# SR1PCB_2025-01-03.net
KiCad netlist of a schematic drawn in Altium Designer
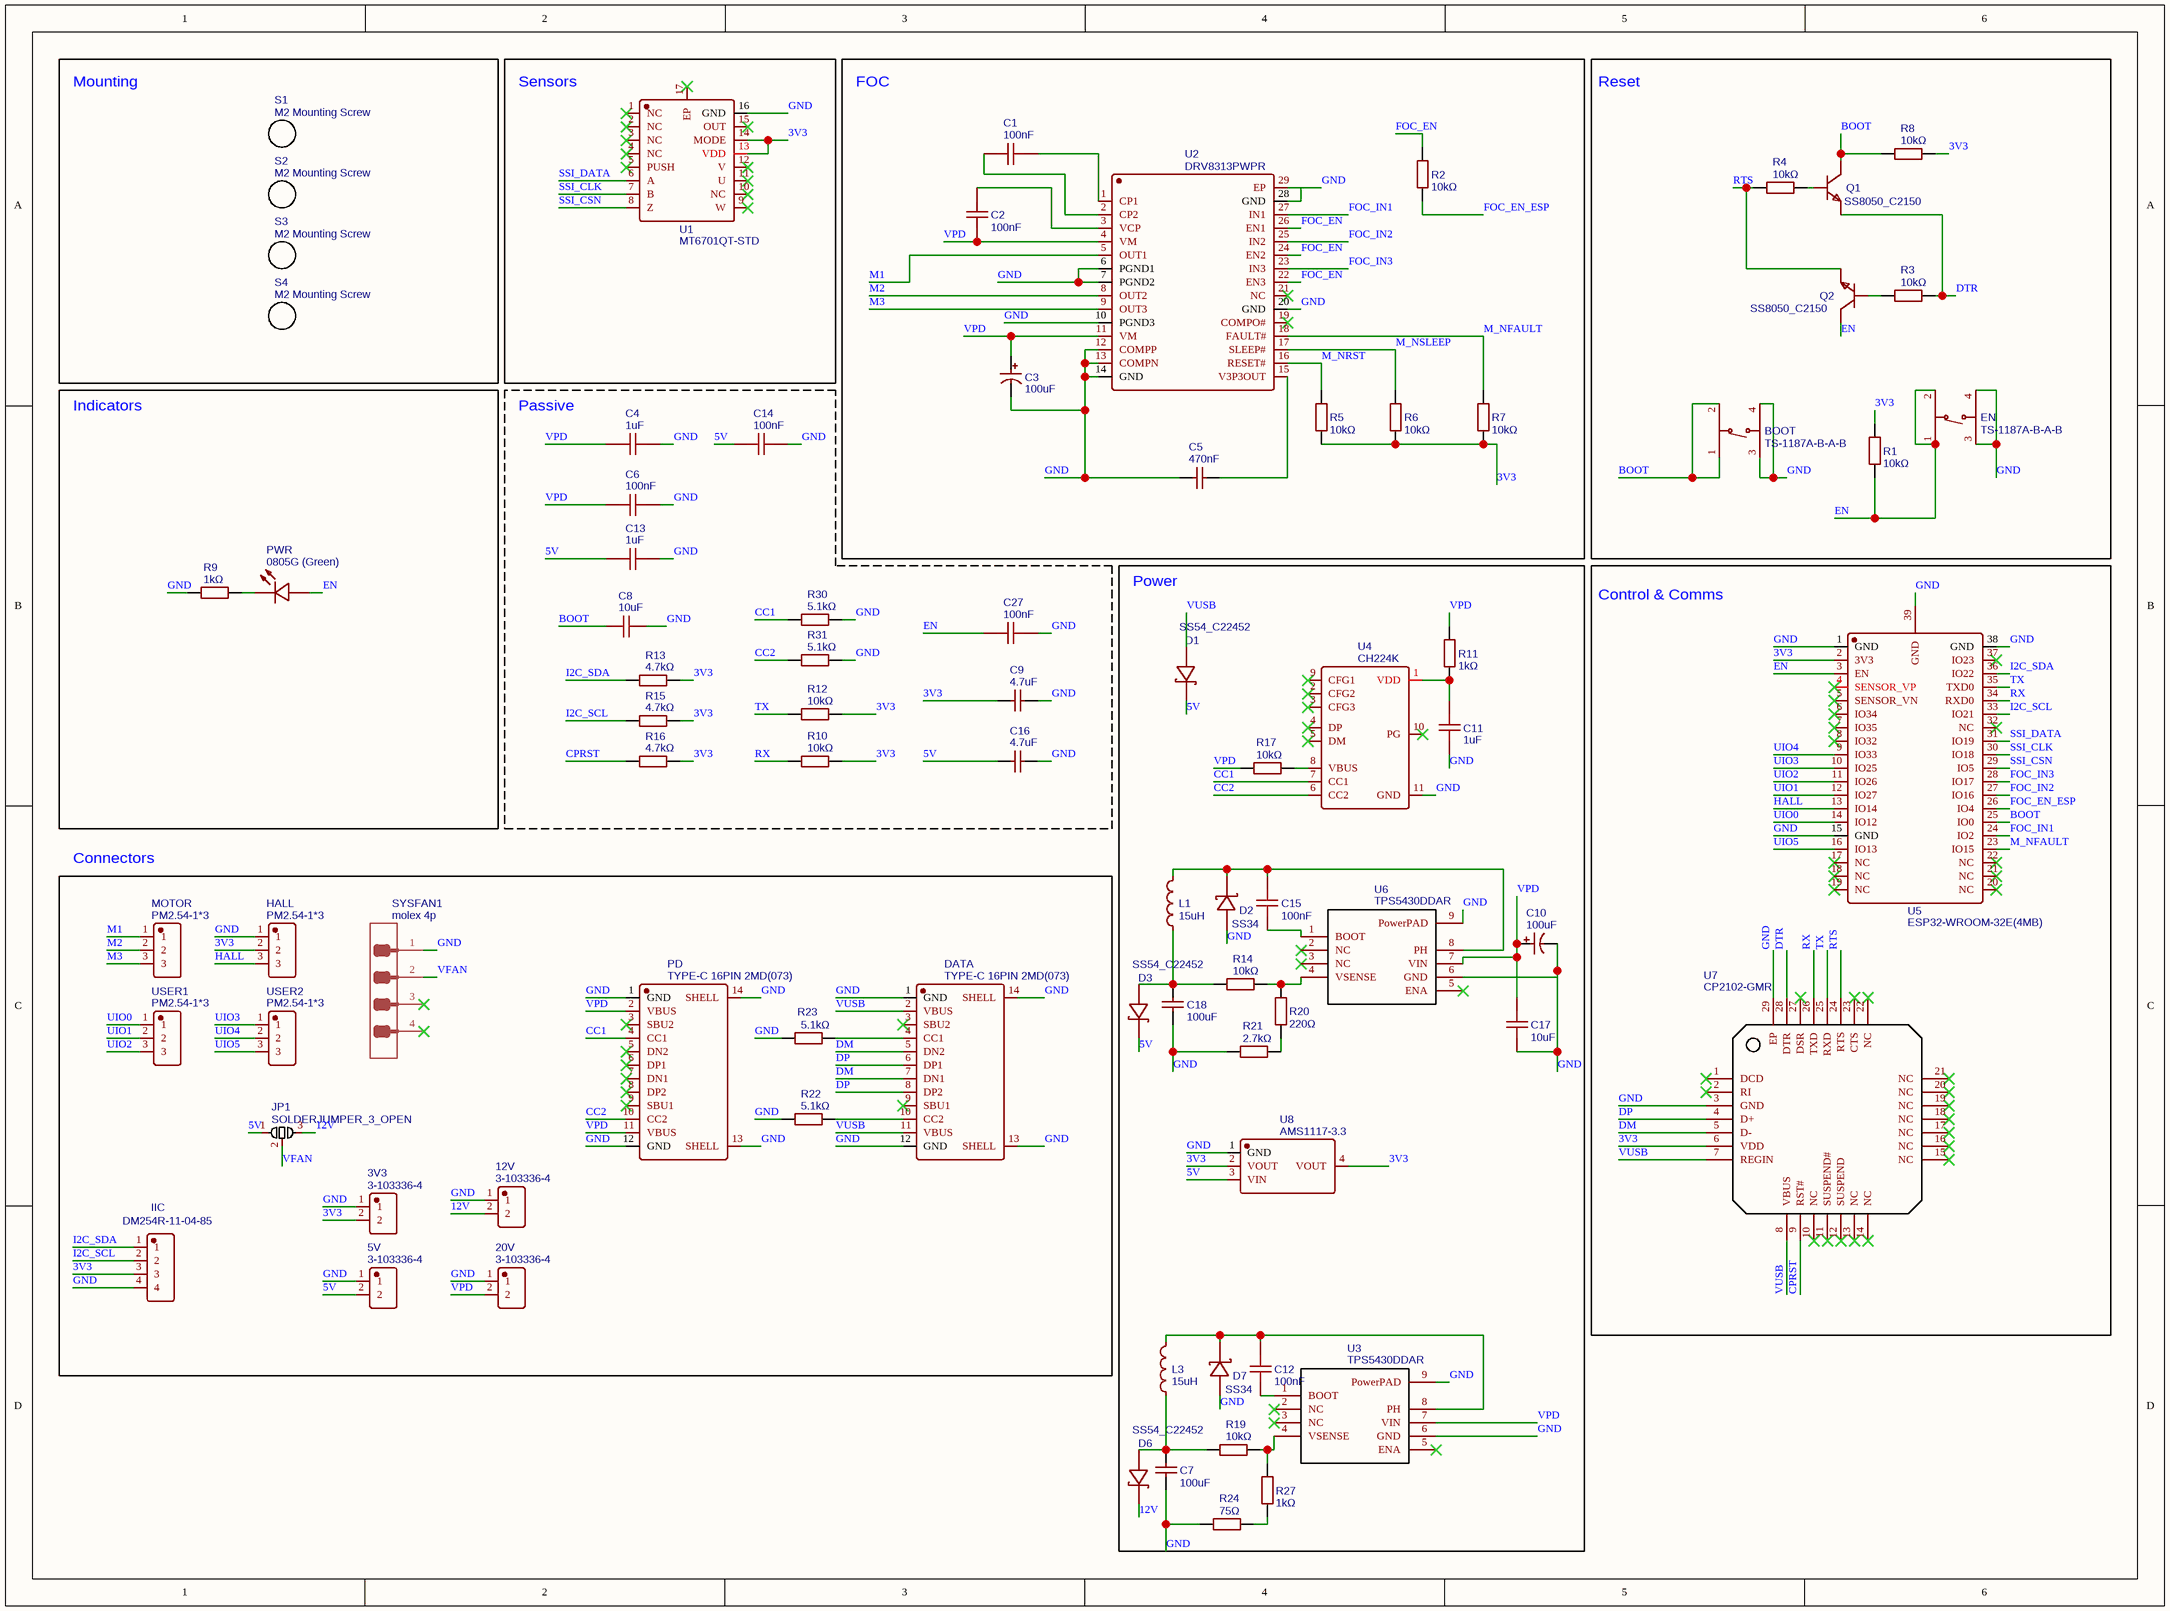
[diagram p0: SR1PCB_2025-01-03.schdoc]

(export (version "E")
  (design (tool "Eeschema 10.0.6"))
  (components
    (comp (ref "3V3")
      (value "3-103336-4")
      (fields (field (name "MANUFACTURER") "TE Connectivity(泰科电子)") (field (name "CONTRIBUTOR") "lcsc"))
      (libsource (lib "altium-import") (part "root_0_3-103336-4_"))
    )
    (comp (ref "5V")
      (value "3-103336-4")
      (fields (field (name "MANUFACTURER") "TE Connectivity(泰科电子)") (field (name "CONTRIBUTOR") "lcsc"))
      (libsource (lib "altium-import") (part "root_0_3-103336-4_"))
    )
    (comp (ref "12V")
      (value "3-103336-4")
      (fields (field (name "MANUFACTURER") "TE Connectivity(泰科电子)") (field (name "CONTRIBUTOR") "lcsc"))
      (libsource (lib "altium-import") (part "root_0_3-103336-4_"))
    )
    (comp (ref "20V")
      (value "3-103336-4")
      (fields (field (name "MANUFACTURER") "TE Connectivity(泰科电子)") (field (name "CONTRIBUTOR") "lcsc"))
      (libsource (lib "altium-import") (part "root_0_3-103336-4_"))
    )
    (comp (ref "BOOT")
      (value "TS-1187A-B-A-B")
      (fields (field (name "MANUFACTURER") "XKB Connectivity(中国星坤)") (field (name "CONTRIBUTOR") "LCSC"))
      (libsource (lib "altium-import") (part "root_1_TS-1187A-B-A-B_"))
    )
    (comp (ref "C1")
      (value "100nF")
      (fields
        (field (name "MANUFACTURER") "YAGEO(国巨)")
        (field (name "MANUFACTURER PART") "CC0603KRX7R9BB104")
      )
      (libsource (lib "altium-import") (part "root_0_100nF_"))
    )
    (comp (ref "C2")
      (value "100nF")
      (fields
        (field (name "MANUFACTURER") "YAGEO(国巨)")
        (field (name "MANUFACTURER PART") "CC0603KRX7R9BB104")
      )
      (libsource (lib "altium-import") (part "root_1_100nF_"))
    )
    (comp (ref "C3")
      (value "100uF")
      (fields
        (field (name "MANUFACTURER") "ROQANG(容强)")
        (field (name "MANUFACTURER PART") "RT1V101M0607")
        (field (name "CONTRIBUTOR") "LCSC")
      )
      (libsource (lib "altium-import") (part "root_3_100uF_"))
    )
    (comp (ref "C4")
      (value "1uF")
      (fields
        (field (name "MANUFACTURER PART") "CL10A105KB8NNNC")
        (field (name "MANUFACTURER") "SAMSUNG(三星)")
      )
      (libsource (lib "altium-import") (part "root_0_1uF_"))
    )
    (comp (ref "C5")
      (value "470nF")
      (fields
        (field (name "MANUFACTURER PART") "CL21B474KBFNNNE")
        (field (name "MANUFACTURER") "SAMSUNG(三星)")
        (field (name "CONTRIBUTOR") "eisendev")
      )
      (libsource (lib "altium-import") (part "root_3_470nF_"))
    )
    (comp (ref "C6")
      (value "100nF")
      (fields
        (field (name "MANUFACTURER") "YAGEO(国巨)")
        (field (name "MANUFACTURER PART") "CC0603KRX7R9BB104")
      )
      (libsource (lib "altium-import") (part "root_0_100nF_"))
    )
    (comp (ref "C7")
      (value "100uF")
      (fields
        (field (name "MANUFACTURER PART") "CL31A107MQHNNNE")
        (field (name "MANUFACTURER") "SAMSUNG(三星)")
      )
      (libsource (lib "altium-import") (part "root_1_100uF_"))
    )
    (comp (ref "C8")
      (value "10uF")
      (fields
        (field (name "MANUFACTURER") "SAMSUNG(三星)")
        (field (name "MANUFACTURER PART") "CL10A106KP8NNNC")
        (field (name "CONTRIBUTOR") "kharchenko.pm")
      )
      (libsource (lib "altium-import") (part "root_0_10uF_"))
    )
    (comp (ref "C9")
      (value "4.7uF")
      (fields
        (field (name "MANUFACTURER PART") "CL05A475MP5NRNC")
        (field (name "MANUFACTURER") "SAMSUNG(三星)")
      )
      (libsource (lib "altium-import") (part "root_0_4.7uF_"))
    )
    (comp (ref "C10")
      (value "100uF")
      (fields
        (field (name "MANUFACTURER") "ROQANG(容强)")
        (field (name "MANUFACTURER PART") "RT1V101M0607")
        (field (name "CONTRIBUTOR") "LCSC")
      )
      (libsource (lib "altium-import") (part "root_0_100uF_"))
    )
    (comp (ref "C11")
      (value "1uF")
      (fields
        (field (name "MANUFACTURER PART") "CL10A105KB8NNNC")
        (field (name "MANUFACTURER") "SAMSUNG(三星)")
      )
      (libsource (lib "altium-import") (part "root_1_1uF_"))
    )
    (comp (ref "C12")
      (value "100nF")
      (fields
        (field (name "MANUFACTURER") "YAGEO(国巨)")
        (field (name "MANUFACTURER PART") "CC0603KRX7R9BB104")
      )
      (libsource (lib "altium-import") (part "root_3_100nF_"))
    )
    (comp (ref "C13")
      (value "1uF")
      (fields
        (field (name "MANUFACTURER PART") "CL10A105KB8NNNC")
        (field (name "MANUFACTURER") "SAMSUNG(三星)")
      )
      (libsource (lib "altium-import") (part "root_0_1uF_"))
    )
    (comp (ref "C14")
      (value "100nF")
      (fields
        (field (name "MANUFACTURER") "YAGEO(国巨)")
        (field (name "MANUFACTURER PART") "CC0603KRX7R9BB104")
      )
      (libsource (lib "altium-import") (part "root_0_100nF_"))
    )
    (comp (ref "C15")
      (value "100nF")
      (fields
        (field (name "MANUFACTURER") "YAGEO(国巨)")
        (field (name "MANUFACTURER PART") "CC0603KRX7R9BB104")
      )
      (libsource (lib "altium-import") (part "root_3_100nF_"))
    )
    (comp (ref "C16")
      (value "4.7uF")
      (fields
        (field (name "MANUFACTURER PART") "CL05A475MP5NRNC")
        (field (name "MANUFACTURER") "SAMSUNG(三星)")
      )
      (libsource (lib "altium-import") (part "root_0_4.7uF_"))
    )
    (comp (ref "C17")
      (value "10uF")
      (fields
        (field (name "MANUFACTURER PART") "CL21A106KAYNNNE")
        (field (name "MANUFACTURER") "SAMSUNG(三星)")
      )
      (libsource (lib "altium-import") (part "root_1_10uF_"))
    )
    (comp (ref "C18")
      (value "100uF")
      (fields
        (field (name "MANUFACTURER PART") "CL31A107MQHNNNE")
        (field (name "MANUFACTURER") "SAMSUNG(三星)")
      )
      (libsource (lib "altium-import") (part "root_1_100uF_"))
    )
    (comp (ref "C27")
      (value "100nF")
      (fields
        (field (name "MANUFACTURER") "YAGEO(国巨)")
        (field (name "MANUFACTURER PART") "CC0603KRX7R9BB104")
      )
      (libsource (lib "altium-import") (part "root_0_100nF_"))
    )
    (comp (ref "D1")
      (value "SS54_C22452")
      (fields
        (field (name "MANUFACTURER PART") "SS54")
        (field (name "MANUFACTURER") "MDD")
        (field (name "CONTRIBUTOR") "mtz8302")
      )
      (libsource (lib "altium-import") (part "root_3_SS54_C22452_"))
    )
    (comp (ref "D2")
      (value "SS34")
      (fields (field (name "MANUFACTURER") "MDD(辰达半导体)"))
      (libsource (lib "altium-import") (part "root_3_SS34_"))
    )
    (comp (ref "D3")
      (value "SS54_C22452")
      (fields
        (field (name "MANUFACTURER PART") "SS54")
        (field (name "MANUFACTURER") "MDD")
        (field (name "CONTRIBUTOR") "mtz8302")
      )
      (libsource (lib "altium-import") (part "root_3_SS54_C22452_"))
    )
    (comp (ref "D6")
      (value "SS54_C22452")
      (fields
        (field (name "MANUFACTURER PART") "SS54")
        (field (name "MANUFACTURER") "MDD")
        (field (name "CONTRIBUTOR") "mtz8302")
      )
      (libsource (lib "altium-import") (part "root_3_SS54_C22452_"))
    )
    (comp (ref "D7")
      (value "SS34")
      (fields (field (name "MANUFACTURER") "MDD(辰达半导体)"))
      (libsource (lib "altium-import") (part "root_3_SS34_"))
    )
    (comp (ref "DATA")
      (value "TYPE-C 16PIN 2MD(073)")
      (fields (field (name "MANUFACTURER") "SHOU HAN(首韩)") (field (name "CONTRIBUTOR") "LCSC"))
      (libsource (lib "altium-import") (part "root_0_TYPE-C 16PIN 2MD(073)_"))
    )
    (comp (ref "EN")
      (value "TS-1187A-B-A-B")
      (fields (field (name "MANUFACTURER") "XKB Connectivity(中国星坤)") (field (name "CONTRIBUTOR") "LCSC"))
      (libsource (lib "altium-import") (part "root_1_TS-1187A-B-A-B_"))
    )
    (comp (ref "HALL")
      (value "PM2.54-1*3")
      (fields (field (name "MANUFACTURER") "ZHOURI(洲日)") (field (name "CONTRIBUTOR") "lcsc"))
      (libsource (lib "altium-import") (part "root_0_PM2.54-1*3_"))
    )
    (comp (ref "IIC")
      (value "DM254R-11-04-85")
      (fields (field (name "MANUFACTURER") "DEALON(德艺隆)") (field (name "CONTRIBUTOR") "LCSC"))
      (libsource (lib "altium-import") (part "root_0_DM254R-11-04-85_"))
    )
    (comp (ref "JP1")
      (value "SOLDERJUMPER_3_OPEN")
      (fields (field (name "CONTRIBUTOR") "mtz8302"))
      (libsource (lib "altium-import") (part "root_0_SOLDERJUMPER_3_OPEN_"))
    )
    (comp (ref "L1")
      (value "15uH")
      (fields
        (field (name "MANUFACTURER") "Sunlord(顺络)")
        (field (name "MANUFACTURER PART") "MWSA0603S-150MT")
        (field (name "CONTRIBUTOR") "LCSC")
      )
      (libsource (lib "altium-import") (part "root_1_15uH_"))
    )
    (comp (ref "L3")
      (value "15uH")
      (fields
        (field (name "MANUFACTURER") "Sunlord(顺络)")
        (field (name "MANUFACTURER PART") "MWSA0603S-150MT")
        (field (name "CONTRIBUTOR") "LCSC")
      )
      (libsource (lib "altium-import") (part "root_1_15uH_"))
    )
    (comp (ref "MOTOR")
      (value "PM2.54-1*3")
      (fields (field (name "MANUFACTURER") "ZHOURI(洲日)") (field (name "CONTRIBUTOR") "lcsc"))
      (libsource (lib "altium-import") (part "root_0_PM2.54-1*3_"))
    )
    (comp (ref "PD")
      (value "TYPE-C 16PIN 2MD(073)")
      (fields (field (name "MANUFACTURER") "SHOU HAN(首韩)") (field (name "CONTRIBUTOR") "LCSC"))
      (libsource (lib "altium-import") (part "root_0_TYPE-C 16PIN 2MD(073)_"))
    )
    (comp (ref "PWR")
      (value "0805G (Green)")
      (fields (field (name "MANUFACTURER") "KENTO") (field (name "MANUFACTURER PART") "KT-0805G"))
      (libsource (lib "altium-import") (part "root_0_0805G (Green)_"))
    )
    (comp (ref "Q1")
      (value "SS8050_C2150")
      (fields (field (name "MANUFACTURER") "CJ(江苏长电/长晶)") (field (name "MANUFACTURER PART") "SS8050"))
      (libsource (lib "altium-import") (part "root_0_SS8050_C2150_"))
    )
    (comp (ref "Q2")
      (value "SS8050_C2150")
      (fields (field (name "MANUFACTURER") "CJ(江苏长电/长晶)") (field (name "MANUFACTURER PART") "SS8050"))
      (libsource (lib "altium-import") (part "root_2_SS8050_C2150_"))
    )
    (comp (ref "R1")
      (value "10kΩ")
      (fields
        (field (name "MANUFACTURER") "UNI-ROYAL(厚声)")
        (field (name "MANUFACTURER PART") "0402WGF1002TCE")
      )
      (libsource (lib "altium-import") (part "root_1_10kΩ_"))
    )
    (comp (ref "R2")
      (value "10kΩ")
      (fields
        (field (name "MANUFACTURER") "UNI-ROYAL(厚声)")
        (field (name "MANUFACTURER PART") "0603WAF1002T5E")
      )
      (libsource (lib "altium-import") (part "root_1_10kΩ_"))
    )
    (comp (ref "R3")
      (value "10kΩ")
      (fields
        (field (name "MANUFACTURER") "UNI-ROYAL(厚声)")
        (field (name "MANUFACTURER PART") "0402WGF1002TCE")
      )
      (libsource (lib "altium-import") (part "root_2_10kΩ_"))
    )
    (comp (ref "R4")
      (value "10kΩ")
      (fields
        (field (name "MANUFACTURER") "UNI-ROYAL(厚声)")
        (field (name "MANUFACTURER PART") "0402WGF1002TCE")
      )
      (libsource (lib "altium-import") (part "root_2_10kΩ_"))
    )
    (comp (ref "R5")
      (value "10kΩ")
      (fields
        (field (name "MANUFACTURER") "UNI-ROYAL(厚声)")
        (field (name "MANUFACTURER PART") "0402WGF1002TCE")
      )
      (libsource (lib "altium-import") (part "root_1_10kΩ_"))
    )
    (comp (ref "R6")
      (value "10kΩ")
      (fields
        (field (name "MANUFACTURER") "UNI-ROYAL(厚声)")
        (field (name "MANUFACTURER PART") "0402WGF1002TCE")
      )
      (libsource (lib "altium-import") (part "root_1_10kΩ_"))
    )
    (comp (ref "R7")
      (value "10kΩ")
      (fields
        (field (name "MANUFACTURER") "UNI-ROYAL(厚声)")
        (field (name "MANUFACTURER PART") "0402WGF1002TCE")
      )
      (libsource (lib "altium-import") (part "root_1_10kΩ_"))
    )
    (comp (ref "R8")
      (value "10kΩ")
      (fields
        (field (name "MANUFACTURER") "UNI-ROYAL(厚声)")
        (field (name "MANUFACTURER PART") "0402WGF1002TCE")
      )
      (libsource (lib "altium-import") (part "root_2_10kΩ_"))
    )
    (comp (ref "R9")
      (value "1kΩ")
      (fields
        (field (name "MANUFACTURER") "UNI-ROYAL(厚声)")
        (field (name "MANUFACTURER PART") "0402WGF1001TCE")
      )
      (libsource (lib "altium-import") (part "root_2_1kΩ_"))
    )
    (comp (ref "R10")
      (value "10kΩ")
      (fields
        (field (name "MANUFACTURER") "UNI-ROYAL(厚声)")
        (field (name "MANUFACTURER PART") "0402WGF1002TCE")
      )
      (libsource (lib "altium-import") (part "root_0_10kΩ_"))
    )
    (comp (ref "R11")
      (value "1kΩ")
      (fields
        (field (name "MANUFACTURER") "UNI-ROYAL(厚声)")
        (field (name "MANUFACTURER PART") "0402WGF1001TCE")
      )
      (libsource (lib "altium-import") (part "root_1_1kΩ_"))
    )
    (comp (ref "R12")
      (value "10kΩ")
      (fields
        (field (name "MANUFACTURER") "UNI-ROYAL(厚声)")
        (field (name "MANUFACTURER PART") "0402WGF1002TCE")
      )
      (libsource (lib "altium-import") (part "root_0_10kΩ_"))
    )
    (comp (ref "R13")
      (value "4.7kΩ")
      (fields
        (field (name "MANUFACTURER") "UNI-ROYAL(厚声)")
        (field (name "MANUFACTURER PART") "0402WGF4701TCE")
      )
      (libsource (lib "altium-import") (part "root_0_4.7kΩ_"))
    )
    (comp (ref "R14")
      (value "10kΩ")
      (fields
        (field (name "MANUFACTURER") "UNI-ROYAL(厚声)")
        (field (name "MANUFACTURER PART") "0402WGF1002TCE")
      )
      (libsource (lib "altium-import") (part "root_0_10kΩ_"))
    )
    (comp (ref "R15")
      (value "4.7kΩ")
      (fields
        (field (name "MANUFACTURER") "UNI-ROYAL(厚声)")
        (field (name "MANUFACTURER PART") "0402WGF4701TCE")
      )
      (libsource (lib "altium-import") (part "root_0_4.7kΩ_"))
    )
    (comp (ref "R16")
      (value "4.7kΩ")
      (fields
        (field (name "MANUFACTURER") "UNI-ROYAL(厚声)")
        (field (name "MANUFACTURER PART") "0402WGF4701TCE")
      )
      (libsource (lib "altium-import") (part "root_0_4.7kΩ_"))
    )
    (comp (ref "R17")
      (value "10kΩ")
      (fields
        (field (name "MANUFACTURER") "UNI-ROYAL(厚声)")
        (field (name "MANUFACTURER PART") "0402WGF1002TCE")
      )
      (libsource (lib "altium-import") (part "root_2_10kΩ_"))
    )
    (comp (ref "R19")
      (value "10kΩ")
      (fields
        (field (name "MANUFACTURER") "UNI-ROYAL(厚声)")
        (field (name "MANUFACTURER PART") "0402WGF1002TCE")
      )
      (libsource (lib "altium-import") (part "root_0_10kΩ_"))
    )
    (comp (ref "R20")
      (value "220Ω")
      (fields
        (field (name "MANUFACTURER") "UNI-ROYAL(厚声)")
        (field (name "MANUFACTURER PART") "0603WAF2200T5E")
      )
      (libsource (lib "altium-import") (part "root_1_220Ω_"))
    )
    (comp (ref "R21")
      (value "2.7kΩ")
      (fields
        (field (name "MANUFACTURER") "UniOhm")
        (field (name "MANUFACTURER PART") "0603WAF2701T5E")
        (field (name "CONTRIBUTOR") "kliu24")
      )
      (libsource (lib "altium-import") (part "root_0_2.7kΩ_"))
    )
    (comp (ref "R22")
      (value "5.1kΩ")
      (fields
        (field (name "MANUFACTURER") "UNI-ROYAL(厚声)")
        (field (name "MANUFACTURER PART") "0402WGF5101TCE")
      )
      (libsource (lib "altium-import") (part "root_0_5.1kΩ_"))
    )
    (comp (ref "R23")
      (value "5.1kΩ")
      (fields
        (field (name "MANUFACTURER") "UNI-ROYAL(厚声)")
        (field (name "MANUFACTURER PART") "0402WGF5101TCE")
      )
      (libsource (lib "altium-import") (part "root_0_5.1kΩ_"))
    )
    (comp (ref "R24")
      (value "75Ω")
      (fields
        (field (name "MANUFACTURER") "UNI-ROYAL(厚声)")
        (field (name "MANUFACTURER PART") "0603WAF750JT5E")
      )
      (libsource (lib "altium-import") (part "root_0_75Ω_"))
    )
    (comp (ref "R27")
      (value "1kΩ")
      (fields
        (field (name "MANUFACTURER") "UNI-ROYAL(厚声)")
        (field (name "MANUFACTURER PART") "0603WAF1001T5E")
      )
      (libsource (lib "altium-import") (part "root_1_1kΩ_"))
    )
    (comp (ref "R30")
      (value "5.1kΩ")
      (fields
        (field (name "MANUFACTURER") "UNI-ROYAL(厚声)")
        (field (name "MANUFACTURER PART") "0402WGF5101TCE")
      )
      (libsource (lib "altium-import") (part "root_0_5.1kΩ_"))
    )
    (comp (ref "R31")
      (value "5.1kΩ")
      (fields
        (field (name "MANUFACTURER") "UNI-ROYAL(厚声)")
        (field (name "MANUFACTURER PART") "0402WGF5101TCE")
      )
      (libsource (lib "altium-import") (part "root_0_5.1kΩ_"))
    )
    (comp (ref "S1")
      (value "M2 Mounting Screw")
      (fields (field (name "CONTRIBUTOR") "Dayat -"))
      (libsource (lib "altium-import") (part "root_0_M2 Mounting Screw_"))
    )
    (comp (ref "S2")
      (value "M2 Mounting Screw")
      (fields (field (name "CONTRIBUTOR") "Dayat -"))
      (libsource (lib "altium-import") (part "root_0_M2 Mounting Screw_"))
    )
    (comp (ref "S3")
      (value "M2 Mounting Screw")
      (fields (field (name "CONTRIBUTOR") "Dayat -"))
      (libsource (lib "altium-import") (part "root_0_M2 Mounting Screw_"))
    )
    (comp (ref "S4")
      (value "M2 Mounting Screw")
      (fields (field (name "CONTRIBUTOR") "Dayat -"))
      (libsource (lib "altium-import") (part "root_0_M2 Mounting Screw_"))
    )
    (comp (ref "SYSFAN1")
      (value "molex 4p")
      (fields (field (name "CONTRIBUTOR") "delil1220"))
      (libsource (lib "altium-import") (part "root_0_molex 4p_"))
    )
    (comp (ref "U1")
      (value "MT6701QT-STD")
      (fields (field (name "MANUFACTURER") "MagnTek(麦歌恩)") (field (name "CONTRIBUTOR") "LCSC"))
      (libsource (lib "altium-import") (part "root_0_MT6701QT-STD_"))
    )
    (comp (ref "U2")
      (value "DRV8313PWPR")
      (fields (field (name "MANUFACTURER") "Texas Instruments") (field (name "CONTRIBUTOR") "LCSC"))
      (libsource (lib "altium-import") (part "root_0_DRV8313PWPR_"))
    )
    (comp (ref "U3")
      (value "TPS5430DDAR")
      (fields (field (name "MANUFACTURER") "TI(德州仪器)"))
      (libsource (lib "altium-import") (part "root_0_TPS5430DDAR_"))
    )
    (comp (ref "U4")
      (value "CH224K")
      (fields (field (name "MANUFACTURER") "WCH(南京沁恒)") (field (name "CONTRIBUTOR") "lcsc"))
      (libsource (lib "altium-import") (part "root_0_CH224K_"))
    )
    (comp (ref "U5")
      (value "ESP32-WROOM-32E(4MB)")
      (fields
        (field (name "MANUFACTURER") "ESPRESSIF(乐鑫)")
        (field (name "MANUFACTURER PART") "ESP32-WROOM-32E-N4")
        (field (name "CONTRIBUTOR") "LCSC")
      )
      (libsource (lib "altium-import") (part "root_0_ESP32-WROOM-32E(4MB)_"))
    )
    (comp (ref "U6")
      (value "TPS5430DDAR")
      (fields (field (name "MANUFACTURER") "TI(德州仪器)"))
      (libsource (lib "altium-import") (part "root_0_TPS5430DDAR_"))
    )
    (comp (ref "U7")
      (value "CP2102-GMR")
      (fields (field (name "MANUFACTURER") "SKYWORKS/SILICON LABS(芯科)"))
      (libsource (lib "altium-import") (part "root_0_CP2102-GMR_"))
    )
    (comp (ref "U8")
      (value "AMS1117-3.3")
      (fields (field (name "MANUFACTURER") "AMS"))
      (libsource (lib "altium-import") (part "root_0_AMS1117-3.3_"))
    )
    (comp (ref "USER1")
      (value "PM2.54-1*3")
      (fields (field (name "MANUFACTURER") "ZHOURI(洲日)") (field (name "CONTRIBUTOR") "lcsc"))
      (libsource (lib "altium-import") (part "root_0_PM2.54-1*3_"))
    )
    (comp (ref "USER2")
      (value "PM2.54-1*3")
      (fields (field (name "MANUFACTURER") "ZHOURI(洲日)") (field (name "CONTRIBUTOR") "lcsc"))
      (libsource (lib "altium-import") (part "root_0_PM2.54-1*3_"))
    )
  )
  (nets
    (net (code "1") (name "/3V3") (class "Default")
      (node (ref "3V3") (pin "2") (pinfunction "2_2") (pintype "passive"))
      (node (ref "C9") (pin "1") (pinfunction "1_1") (pintype "passive"))
      (node (ref "HALL") (pin "2") (pinfunction "2_2") (pintype "passive"))
      (node (ref "IIC") (pin "3") (pinfunction "3_3") (pintype "passive"))
      (node (ref "R1") (pin "2") (pinfunction "2_2") (pintype "passive"))
      (node (ref "R10") (pin "2") (pinfunction "2_2") (pintype "passive"))
      (node (ref "R12") (pin "2") (pinfunction "2_2") (pintype "passive"))
      (node (ref "R13") (pin "2") (pinfunction "2_2") (pintype "passive"))
      (node (ref "R15") (pin "2") (pinfunction "2_2") (pintype "passive"))
      (node (ref "R16") (pin "2") (pinfunction "2_2") (pintype "passive"))
      (node (ref "R5") (pin "1") (pinfunction "1_1") (pintype "passive"))
      (node (ref "R6") (pin "1") (pinfunction "1_1") (pintype "passive"))
      (node (ref "R7") (pin "1") (pinfunction "1_1") (pintype "passive"))
      (node (ref "R8") (pin "1") (pinfunction "1_1") (pintype "passive"))
      (node (ref "U1") (pin "13") (pinfunction "VDD_13") (pintype "passive"))
      (node (ref "U1") (pin "14") (pinfunction "MODE_14") (pintype "passive"))
      (node (ref "U5") (pin "2") (pinfunction "3V3_2") (pintype "passive"))
      (node (ref "U7") (pin "6") (pinfunction "VDD_6") (pintype "passive"))
      (node (ref "U8") (pin "2") (pinfunction "VOUT_2") (pintype "passive"))
      (node (ref "U8") (pin "4") (pinfunction "VOUT_4") (pintype "passive"))
    )
    (net (code "2") (name "/5V") (class "Default")
      (node (ref "5V") (pin "2") (pinfunction "2_2") (pintype "passive"))
      (node (ref "C13") (pin "1") (pinfunction "1_1") (pintype "passive"))
      (node (ref "C14") (pin "1") (pinfunction "1_1") (pintype "passive"))
      (node (ref "C16") (pin "1") (pinfunction "1_1") (pintype "passive"))
      (node (ref "D1") (pin "2") (pinfunction "K_2") (pintype "passive"))
      (node (ref "D3") (pin "2") (pinfunction "K_2") (pintype "passive"))
      (node (ref "JP1") (pin "1") (pinfunction "A_1") (pintype "passive"))
      (node (ref "U8") (pin "3") (pinfunction "VIN_3") (pintype "passive"))
    )
    (net (code "3") (name "/12V") (class "Default")
      (node (ref "12V") (pin "2") (pinfunction "2_2") (pintype "passive"))
      (node (ref "D6") (pin "2") (pinfunction "K_2") (pintype "passive"))
      (node (ref "JP1") (pin "3") (pinfunction "B_3") (pintype "passive"))
    )
    (net (code "4") (name "/BOOT") (class "Default")
      (node (ref "BOOT") (pin "1") (pinfunction "A_1") (pintype "passive"))
      (node (ref "BOOT") (pin "2") (pinfunction "B_2") (pintype "passive"))
      (node (ref "C8") (pin "1") (pinfunction "1_1") (pintype "passive"))
      (node (ref "Q1") (pin "3") (pinfunction "C_3") (pintype "passive"))
      (node (ref "R8") (pin "2") (pinfunction "2_2") (pintype "passive"))
      (node (ref "U5") (pin "25") (pinfunction "IO0_25") (pintype "passive"))
    )
    (net (code "5") (name "/CC1") (class "Default")
      (node (ref "PD") (pin "4") (pinfunction "CC1_4") (pintype "passive"))
      (node (ref "R30") (pin "1") (pinfunction "1_1") (pintype "passive"))
      (node (ref "U4") (pin "7") (pinfunction "CC1_7") (pintype "passive"))
    )
    (net (code "6") (name "/CC2") (class "Default")
      (node (ref "PD") (pin "10") (pinfunction "CC2_10") (pintype "passive"))
      (node (ref "R31") (pin "1") (pinfunction "1_1") (pintype "passive"))
      (node (ref "U4") (pin "6") (pinfunction "CC2_6") (pintype "passive"))
    )
    (net (code "7") (name "/CPRST") (class "Default")
      (node (ref "R16") (pin "1") (pinfunction "1_1") (pintype "passive"))
      (node (ref "U7") (pin "9") (pinfunction "RST#_9") (pintype "passive"))
    )
    (net (code "8") (name "/DM") (class "Default")
      (node (ref "DATA") (pin "5") (pinfunction "DN2_5") (pintype "passive"))
      (node (ref "DATA") (pin "7") (pinfunction "DN1_7") (pintype "passive"))
      (node (ref "U7") (pin "5") (pinfunction "D-_5") (pintype "passive"))
    )
    (net (code "9") (name "/DP") (class "Default")
      (node (ref "DATA") (pin "6") (pinfunction "DP1_6") (pintype "passive"))
      (node (ref "DATA") (pin "8") (pinfunction "DP2_8") (pintype "passive"))
      (node (ref "U7") (pin "4") (pinfunction "D+_4") (pintype "passive"))
    )
    (net (code "10") (name "/DTR") (class "Default")
      (node (ref "Q1") (pin "2") (pinfunction "E_2") (pintype "passive"))
      (node (ref "R3") (pin "1") (pinfunction "1_1") (pintype "passive"))
      (node (ref "U7") (pin "28") (pinfunction "DTR_28") (pintype "passive"))
    )
    (net (code "11") (name "/EN") (class "Default")
      (node (ref "C27") (pin "1") (pinfunction "1_1") (pintype "passive"))
      (node (ref "EN") (pin "1") (pinfunction "A_1") (pintype "passive"))
      (node (ref "EN") (pin "2") (pinfunction "B_2") (pintype "passive"))
      (node (ref "PWR") (pin "1") (pinfunction "A_1") (pintype "passive"))
      (node (ref "Q2") (pin "3") (pinfunction "C_3") (pintype "passive"))
      (node (ref "R1") (pin "1") (pinfunction "1_1") (pintype "passive"))
      (node (ref "U5") (pin "3") (pinfunction "EN_3") (pintype "passive"))
    )
    (net (code "12") (name "/FOC_EN") (class "Default")
      (node (ref "R2") (pin "2") (pinfunction "2_2") (pintype "passive"))
      (node (ref "U2") (pin "22") (pinfunction "EN3_22") (pintype "passive"))
      (node (ref "U2") (pin "24") (pinfunction "EN2_24") (pintype "passive"))
      (node (ref "U2") (pin "26") (pinfunction "EN1_26") (pintype "passive"))
    )
    (net (code "13") (name "/FOC_EN_ESP") (class "Default")
      (node (ref "R2") (pin "1") (pinfunction "1_1") (pintype "passive"))
      (node (ref "U5") (pin "26") (pinfunction "IO4_26") (pintype "passive"))
    )
    (net (code "14") (name "/FOC_IN1") (class "Default")
      (node (ref "U2") (pin "27") (pinfunction "IN1_27") (pintype "passive"))
      (node (ref "U5") (pin "24") (pinfunction "IO2_24") (pintype "passive"))
    )
    (net (code "15") (name "/FOC_IN2") (class "Default")
      (node (ref "U2") (pin "25") (pinfunction "IN2_25") (pintype "passive"))
      (node (ref "U5") (pin "27") (pinfunction "IO16_27") (pintype "passive"))
    )
    (net (code "16") (name "/FOC_IN3") (class "Default")
      (node (ref "U2") (pin "23") (pinfunction "IN3_23") (pintype "passive"))
      (node (ref "U5") (pin "28") (pinfunction "IO17_28") (pintype "passive"))
    )
    (net (code "17") (name "/GND") (class "Default")
      (node (ref "12V") (pin "1") (pinfunction "1_1") (pintype "passive"))
      (node (ref "20V") (pin "1") (pinfunction "1_1") (pintype "passive"))
      (node (ref "3V3") (pin "1") (pinfunction "1_1") (pintype "passive"))
      (node (ref "5V") (pin "1") (pinfunction "1_1") (pintype "passive"))
      (node (ref "BOOT") (pin "3") (pinfunction "C_3") (pintype "passive"))
      (node (ref "BOOT") (pin "4") (pinfunction "D_4") (pintype "passive"))
      (node (ref "C10") (pin "2") (pinfunction "2_2") (pintype "passive"))
      (node (ref "C11") (pin "1") (pinfunction "1_1") (pintype "passive"))
      (node (ref "C13") (pin "2") (pinfunction "2_2") (pintype "passive"))
      (node (ref "C14") (pin "2") (pinfunction "2_2") (pintype "passive"))
      (node (ref "C16") (pin "2") (pinfunction "2_2") (pintype "passive"))
      (node (ref "C17") (pin "1") (pinfunction "1_1") (pintype "passive"))
      (node (ref "C18") (pin "1") (pinfunction "1_1") (pintype "passive"))
      (node (ref "C27") (pin "2") (pinfunction "2_2") (pintype "passive"))
      (node (ref "C3") (pin "2") (pinfunction "2_2") (pintype "passive"))
      (node (ref "C4") (pin "2") (pinfunction "2_2") (pintype "passive"))
      (node (ref "C5") (pin "1") (pinfunction "1_1") (pintype "passive"))
      (node (ref "C6") (pin "2") (pinfunction "2_2") (pintype "passive"))
      (node (ref "C7") (pin "1") (pinfunction "1_1") (pintype "passive"))
      (node (ref "C8") (pin "2") (pinfunction "2_2") (pintype "passive"))
      (node (ref "C9") (pin "2") (pinfunction "2_2") (pintype "passive"))
      (node (ref "D2") (pin "2") (pinfunction "A_2") (pintype "passive"))
      (node (ref "D7") (pin "2") (pinfunction "A_2") (pintype "passive"))
      (node (ref "DATA") (pin "1") (pinfunction "GND_1") (pintype "passive"))
      (node (ref "DATA") (pin "12") (pinfunction "GND_12") (pintype "passive"))
      (node (ref "DATA") (pin "13") (pinfunction "SHELL_13") (pintype "passive"))
      (node (ref "DATA") (pin "14") (pinfunction "SHELL_14") (pintype "passive"))
      (node (ref "EN") (pin "3") (pinfunction "C_3") (pintype "passive"))
      (node (ref "EN") (pin "4") (pinfunction "D_4") (pintype "passive"))
      (node (ref "HALL") (pin "1") (pinfunction "1_1") (pintype "passive"))
      (node (ref "IIC") (pin "4") (pinfunction "4_4") (pintype "passive"))
      (node (ref "PD") (pin "1") (pinfunction "GND_1") (pintype "passive"))
      (node (ref "PD") (pin "12") (pinfunction "GND_12") (pintype "passive"))
      (node (ref "PD") (pin "13") (pinfunction "SHELL_13") (pintype "passive"))
      (node (ref "PD") (pin "14") (pinfunction "SHELL_14") (pintype "passive"))
      (node (ref "R21") (pin "2") (pinfunction "2_2") (pintype "passive"))
      (node (ref "R22") (pin "1") (pinfunction "1_1") (pintype "passive"))
      (node (ref "R23") (pin "1") (pinfunction "1_1") (pintype "passive"))
      (node (ref "R24") (pin "1") (pinfunction "1_1") (pintype "passive"))
      (node (ref "R30") (pin "2") (pinfunction "2_2") (pintype "passive"))
      (node (ref "R31") (pin "2") (pinfunction "2_2") (pintype "passive"))
      (node (ref "R9") (pin "2") (pinfunction "2_2") (pintype "passive"))
      (node (ref "SYSFAN1") (pin "1") (pinfunction "1_1") (pintype "passive"))
      (node (ref "U1") (pin "16") (pinfunction "GND_16") (pintype "passive"))
      (node (ref "U2") (pin "10") (pinfunction "PGND3_10") (pintype "passive"))
      (node (ref "U2") (pin "12") (pinfunction "COMPP_12") (pintype "passive"))
      (node (ref "U2") (pin "13") (pinfunction "COMPN_13") (pintype "passive"))
      (node (ref "U2") (pin "14") (pinfunction "GND_14") (pintype "passive"))
      (node (ref "U2") (pin "20") (pinfunction "GND_20") (pintype "passive"))
      (node (ref "U2") (pin "28") (pinfunction "GND_28") (pintype "passive"))
      (node (ref "U2") (pin "29") (pinfunction "EP_29") (pintype "passive"))
      (node (ref "U2") (pin "6") (pinfunction "PGND1_6") (pintype "passive"))
      (node (ref "U2") (pin "7") (pinfunction "PGND2_7") (pintype "passive"))
      (node (ref "U3") (pin "6") (pinfunction "GND_6") (pintype "passive"))
      (node (ref "U3") (pin "9") (pinfunction "PowerPAD_9") (pintype "passive"))
      (node (ref "U4") (pin "11") (pinfunction "GND_11") (pintype "passive"))
      (node (ref "U5") (pin "1") (pinfunction "GND_1") (pintype "passive"))
      (node (ref "U5") (pin "15") (pinfunction "GND_15") (pintype "passive"))
      (node (ref "U5") (pin "38") (pinfunction "GND_38") (pintype "passive"))
      (node (ref "U5") (pin "39") (pinfunction "GND_39") (pintype "passive"))
      (node (ref "U6") (pin "6") (pinfunction "GND_6") (pintype "passive"))
      (node (ref "U6") (pin "9") (pinfunction "PowerPAD_9") (pintype "passive"))
      (node (ref "U7") (pin "29") (pinfunction "EP_29") (pintype "passive"))
      (node (ref "U7") (pin "3") (pinfunction "GND_3") (pintype "passive"))
      (node (ref "U8") (pin "1") (pinfunction "GND_1") (pintype "passive"))
    )
    (net (code "18") (name "/HALL") (class "Default")
      (node (ref "HALL") (pin "3") (pinfunction "3_3") (pintype "passive"))
      (node (ref "U5") (pin "13") (pinfunction "IO14_13") (pintype "passive"))
    )
    (net (code "19") (name "/I2C_SCL") (class "Default")
      (node (ref "IIC") (pin "2") (pinfunction "2_2") (pintype "passive"))
      (node (ref "R15") (pin "1") (pinfunction "1_1") (pintype "passive"))
      (node (ref "U5") (pin "33") (pinfunction "IO21_33") (pintype "passive"))
    )
    (net (code "20") (name "/I2C_SDA") (class "Default")
      (node (ref "IIC") (pin "1") (pinfunction "1_1") (pintype "passive"))
      (node (ref "R13") (pin "1") (pinfunction "1_1") (pintype "passive"))
      (node (ref "U5") (pin "36") (pinfunction "IO22_36") (pintype "passive"))
    )
    (net (code "21") (name "/M1") (class "Default")
      (node (ref "MOTOR") (pin "1") (pinfunction "1_1") (pintype "passive"))
      (node (ref "U2") (pin "5") (pinfunction "OUT1_5") (pintype "passive"))
    )
    (net (code "22") (name "/M2") (class "Default")
      (node (ref "MOTOR") (pin "2") (pinfunction "2_2") (pintype "passive"))
      (node (ref "U2") (pin "8") (pinfunction "OUT2_8") (pintype "passive"))
    )
    (net (code "23") (name "/M3") (class "Default")
      (node (ref "MOTOR") (pin "3") (pinfunction "3_3") (pintype "passive"))
      (node (ref "U2") (pin "9") (pinfunction "OUT3_9") (pintype "passive"))
    )
    (net (code "24") (name "/M_NFAULT") (class "Default")
      (node (ref "R7") (pin "2") (pinfunction "2_2") (pintype "passive"))
      (node (ref "U2") (pin "18") (pinfunction "FAULT#_18") (pintype "passive"))
      (node (ref "U5") (pin "23") (pinfunction "IO15_23") (pintype "passive"))
    )
    (net (code "25") (name "/M_NRST") (class "Default")
      (node (ref "R5") (pin "2") (pinfunction "2_2") (pintype "passive"))
      (node (ref "U2") (pin "16") (pinfunction "RESET#_16") (pintype "passive"))
    )
    (net (code "26") (name "/M_NSLEEP") (class "Default")
      (node (ref "R6") (pin "2") (pinfunction "2_2") (pintype "passive"))
      (node (ref "U2") (pin "17") (pinfunction "SLEEP#_17") (pintype "passive"))
    )
    (net (code "27") (name "/RTS") (class "Default")
      (node (ref "Q2") (pin "2") (pinfunction "E_2") (pintype "passive"))
      (node (ref "R4") (pin "2") (pinfunction "2_2") (pintype "passive"))
      (node (ref "U7") (pin "24") (pinfunction "RTS_24") (pintype "passive"))
    )
    (net (code "28") (name "/RX") (class "Default")
      (node (ref "R10") (pin "1") (pinfunction "1_1") (pintype "passive"))
      (node (ref "U5") (pin "34") (pinfunction "RXD0_34") (pintype "passive"))
      (node (ref "U7") (pin "26") (pinfunction "TXD_26") (pintype "passive"))
    )
    (net (code "29") (name "/SSI_CLK") (class "Default")
      (node (ref "U1") (pin "7") (pinfunction "B_7") (pintype "passive"))
      (node (ref "U5") (pin "30") (pinfunction "IO18_30") (pintype "passive"))
    )
    (net (code "30") (name "/SSI_CSN") (class "Default")
      (node (ref "U1") (pin "8") (pinfunction "Z_8") (pintype "passive"))
      (node (ref "U5") (pin "29") (pinfunction "IO5_29") (pintype "passive"))
    )
    (net (code "31") (name "/SSI_DATA") (class "Default")
      (node (ref "U1") (pin "6") (pinfunction "A_6") (pintype "passive"))
      (node (ref "U5") (pin "31") (pinfunction "IO19_31") (pintype "passive"))
    )
    (net (code "32") (name "/TX") (class "Default")
      (node (ref "R12") (pin "1") (pinfunction "1_1") (pintype "passive"))
      (node (ref "U5") (pin "35") (pinfunction "TXD0_35") (pintype "passive"))
      (node (ref "U7") (pin "25") (pinfunction "RXD_25") (pintype "passive"))
    )
    (net (code "33") (name "/UIO0") (class "Default")
      (node (ref "U5") (pin "14") (pinfunction "IO12_14") (pintype "passive"))
      (node (ref "USER1") (pin "1") (pinfunction "1_1") (pintype "passive"))
    )
    (net (code "34") (name "/UIO1") (class "Default")
      (node (ref "U5") (pin "12") (pinfunction "IO27_12") (pintype "passive"))
      (node (ref "USER1") (pin "2") (pinfunction "2_2") (pintype "passive"))
    )
    (net (code "35") (name "/UIO2") (class "Default")
      (node (ref "U5") (pin "11") (pinfunction "IO26_11") (pintype "passive"))
      (node (ref "USER1") (pin "3") (pinfunction "3_3") (pintype "passive"))
    )
    (net (code "36") (name "/UIO3") (class "Default")
      (node (ref "U5") (pin "10") (pinfunction "IO25_10") (pintype "passive"))
      (node (ref "USER2") (pin "1") (pinfunction "1_1") (pintype "passive"))
    )
    (net (code "37") (name "/UIO4") (class "Default")
      (node (ref "U5") (pin "9") (pinfunction "IO33_9") (pintype "passive"))
      (node (ref "USER2") (pin "2") (pinfunction "2_2") (pintype "passive"))
    )
    (net (code "38") (name "/UIO5") (class "Default")
      (node (ref "U5") (pin "16") (pinfunction "IO13_16") (pintype "passive"))
      (node (ref "USER2") (pin "3") (pinfunction "3_3") (pintype "passive"))
    )
    (net (code "39") (name "/VFAN") (class "Default")
      (node (ref "JP1") (pin "2") (pinfunction "C_2") (pintype "passive"))
      (node (ref "SYSFAN1") (pin "2") (pinfunction "2_2") (pintype "passive"))
    )
    (net (code "40") (name "/VPD") (class "Default")
      (node (ref "20V") (pin "2") (pinfunction "2_2") (pintype "passive"))
      (node (ref "C10") (pin "1") (pinfunction "1_1") (pintype "passive"))
      (node (ref "C17") (pin "2") (pinfunction "2_2") (pintype "passive"))
      (node (ref "C2") (pin "1") (pinfunction "1_1") (pintype "passive"))
      (node (ref "C3") (pin "1") (pinfunction "1_1") (pintype "passive"))
      (node (ref "C4") (pin "1") (pinfunction "1_1") (pintype "passive"))
      (node (ref "C6") (pin "1") (pinfunction "1_1") (pintype "passive"))
      (node (ref "PD") (pin "11") (pinfunction "VBUS_11") (pintype "passive"))
      (node (ref "PD") (pin "2") (pinfunction "VBUS_2") (pintype "passive"))
      (node (ref "R11") (pin "2") (pinfunction "2_2") (pintype "passive"))
      (node (ref "R17") (pin "2") (pinfunction "2_2") (pintype "passive"))
      (node (ref "U2") (pin "11") (pinfunction "VM_11") (pintype "passive"))
      (node (ref "U2") (pin "4") (pinfunction "VM_4") (pintype "passive"))
      (node (ref "U3") (pin "7") (pinfunction "VIN_7") (pintype "passive"))
      (node (ref "U6") (pin "7") (pinfunction "VIN_7") (pintype "passive"))
    )
    (net (code "41") (name "/VUSB") (class "Default")
      (node (ref "D1") (pin "1") (pinfunction "A_1") (pintype "passive"))
      (node (ref "DATA") (pin "11") (pinfunction "VBUS_11") (pintype "passive"))
      (node (ref "DATA") (pin "2") (pinfunction "VBUS_2") (pintype "passive"))
      (node (ref "U7") (pin "7") (pinfunction "REGIN_7") (pintype "passive"))
      (node (ref "U7") (pin "8") (pinfunction "VBUS_8") (pintype "passive"))
    )
    (net (code "42") (name "Net-(D2-K)") (class "Default")
      (node (ref "C15") (pin "1") (pinfunction "1_1") (pintype "passive"))
      (node (ref "D2") (pin "1") (pinfunction "K_1") (pintype "passive"))
      (node (ref "L1") (pin "2") (pinfunction "2_2") (pintype "passive"))
      (node (ref "U6") (pin "8") (pinfunction "PH_8") (pintype "passive"))
    )
    (net (code "43") (name "Net-(D3-A)") (class "Default")
      (node (ref "C18") (pin "2") (pinfunction "2_2") (pintype "passive"))
      (node (ref "D3") (pin "1") (pinfunction "A_1") (pintype "passive"))
      (node (ref "L1") (pin "1") (pinfunction "1_1") (pintype "passive"))
      (node (ref "R14") (pin "1") (pinfunction "1_1") (pintype "passive"))
    )
    (net (code "44") (name "Net-(D6-A)") (class "Default")
      (node (ref "C7") (pin "2") (pinfunction "2_2") (pintype "passive"))
      (node (ref "D6") (pin "1") (pinfunction "A_1") (pintype "passive"))
      (node (ref "L3") (pin "1") (pinfunction "1_1") (pintype "passive"))
      (node (ref "R19") (pin "1") (pinfunction "1_1") (pintype "passive"))
    )
    (net (code "45") (name "Net-(D7-K)") (class "Default")
      (node (ref "C12") (pin "1") (pinfunction "1_1") (pintype "passive"))
      (node (ref "D7") (pin "1") (pinfunction "K_1") (pintype "passive"))
      (node (ref "L3") (pin "2") (pinfunction "2_2") (pintype "passive"))
      (node (ref "U3") (pin "8") (pinfunction "PH_8") (pintype "passive"))
    )
    (net (code "46") (name "Net-(DATA-CC1)") (class "Default")
      (node (ref "DATA") (pin "4") (pinfunction "CC1_4") (pintype "passive"))
      (node (ref "R23") (pin "2") (pinfunction "2_2") (pintype "passive"))
    )
    (net (code "47") (name "Net-(DATA-CC2)") (class "Default")
      (node (ref "DATA") (pin "10") (pinfunction "CC2_10") (pintype "passive"))
      (node (ref "R22") (pin "2") (pinfunction "2_2") (pintype "passive"))
    )
    (net (code "48") (name "Net-(PWR-K)") (class "Default")
      (node (ref "PWR") (pin "2") (pinfunction "K_2") (pintype "passive"))
      (node (ref "R9") (pin "1") (pinfunction "1_1") (pintype "passive"))
    )
    (net (code "49") (name "Net-(Q1-B)") (class "Default")
      (node (ref "Q1") (pin "1") (pinfunction "B_1") (pintype "passive"))
      (node (ref "R4") (pin "1") (pinfunction "1_1") (pintype "passive"))
    )
    (net (code "50") (name "Net-(Q2-B)") (class "Default")
      (node (ref "Q2") (pin "1") (pinfunction "B_1") (pintype "passive"))
      (node (ref "R3") (pin "2") (pinfunction "2_2") (pintype "passive"))
    )
    (net (code "51") (name "Net-(R20-Pad1)") (class "Default")
      (node (ref "R20") (pin "1") (pinfunction "1_1") (pintype "passive"))
      (node (ref "R21") (pin "1") (pinfunction "1_1") (pintype "passive"))
    )
    (net (code "52") (name "Net-(R24-Pad2)") (class "Default")
      (node (ref "R24") (pin "2") (pinfunction "2_2") (pintype "passive"))
      (node (ref "R27") (pin "1") (pinfunction "1_1") (pintype "passive"))
    )
    (net (code "53") (name "Net-(U2-CP1)") (class "Default")
      (node (ref "C1") (pin "2") (pinfunction "2_2") (pintype "passive"))
      (node (ref "U2") (pin "1") (pinfunction "CP1_1") (pintype "passive"))
    )
    (net (code "54") (name "Net-(U2-CP2)") (class "Default")
      (node (ref "C1") (pin "1") (pinfunction "1_1") (pintype "passive"))
      (node (ref "U2") (pin "2") (pinfunction "CP2_2") (pintype "passive"))
    )
    (net (code "55") (name "Net-(U2-V3P3OUT)") (class "Default")
      (node (ref "C5") (pin "2") (pinfunction "2_2") (pintype "passive"))
      (node (ref "U2") (pin "15") (pinfunction "V3P3OUT_15") (pintype "passive"))
    )
    (net (code "56") (name "Net-(U2-VCP)") (class "Default")
      (node (ref "C2") (pin "2") (pinfunction "2_2") (pintype "passive"))
      (node (ref "U2") (pin "3") (pinfunction "VCP_3") (pintype "passive"))
    )
    (net (code "57") (name "Net-(U3-BOOT)") (class "Default")
      (node (ref "C12") (pin "2") (pinfunction "2_2") (pintype "passive"))
      (node (ref "U3") (pin "1") (pinfunction "BOOT_1") (pintype "passive"))
    )
    (net (code "58") (name "Net-(U3-VSENSE)") (class "Default")
      (node (ref "R19") (pin "2") (pinfunction "2_2") (pintype "passive"))
      (node (ref "R27") (pin "2") (pinfunction "2_2") (pintype "passive"))
      (node (ref "U3") (pin "4") (pinfunction "VSENSE_4") (pintype "passive"))
    )
    (net (code "59") (name "Net-(U4-VBUS)") (class "Default")
      (node (ref "R17") (pin "1") (pinfunction "1_1") (pintype "passive"))
      (node (ref "U4") (pin "8") (pinfunction "VBUS_8") (pintype "passive"))
    )
    (net (code "60") (name "Net-(U4-VDD)") (class "Default")
      (node (ref "C11") (pin "2") (pinfunction "2_2") (pintype "passive"))
      (node (ref "R11") (pin "1") (pinfunction "1_1") (pintype "passive"))
      (node (ref "U4") (pin "1") (pinfunction "VDD_1") (pintype "passive"))
    )
    (net (code "61") (name "Net-(U6-BOOT)") (class "Default")
      (node (ref "C15") (pin "2") (pinfunction "2_2") (pintype "passive"))
      (node (ref "U6") (pin "1") (pinfunction "BOOT_1") (pintype "passive"))
    )
    (net (code "62") (name "Net-(U6-VSENSE)") (class "Default")
      (node (ref "R14") (pin "2") (pinfunction "2_2") (pintype "passive"))
      (node (ref "R20") (pin "2") (pinfunction "2_2") (pintype "passive"))
      (node (ref "U6") (pin "4") (pinfunction "VSENSE_4") (pintype "passive"))
    )
    (net (code "63") (name "unconnected-(DATA-SBU1-Pad9)") (class "Default")
      (node (ref "DATA") (pin "9") (pinfunction "SBU1_9") (pintype "passive+no_connect"))
    )
    (net (code "64") (name "unconnected-(DATA-SBU2-Pad3)") (class "Default")
      (node (ref "DATA") (pin "3") (pinfunction "SBU2_3") (pintype "passive+no_connect"))
    )
    (net (code "65") (name "unconnected-(PD-DN1-Pad7)") (class "Default")
      (node (ref "PD") (pin "7") (pinfunction "DN1_7") (pintype "passive+no_connect"))
    )
    (net (code "66") (name "unconnected-(PD-DN2-Pad5)") (class "Default")
      (node (ref "PD") (pin "5") (pinfunction "DN2_5") (pintype "passive+no_connect"))
    )
    (net (code "67") (name "unconnected-(PD-DP1-Pad6)") (class "Default")
      (node (ref "PD") (pin "6") (pinfunction "DP1_6") (pintype "passive+no_connect"))
    )
    (net (code "68") (name "unconnected-(PD-DP2-Pad8)") (class "Default")
      (node (ref "PD") (pin "8") (pinfunction "DP2_8") (pintype "passive+no_connect"))
    )
    (net (code "69") (name "unconnected-(PD-SBU1-Pad9)") (class "Default")
      (node (ref "PD") (pin "9") (pinfunction "SBU1_9") (pintype "passive+no_connect"))
    )
    (net (code "70") (name "unconnected-(PD-SBU2-Pad3)") (class "Default")
      (node (ref "PD") (pin "3") (pinfunction "SBU2_3") (pintype "passive+no_connect"))
    )
    (net (code "71") (name "unconnected-(SYSFAN1-Pad3)") (class "Default")
      (node (ref "SYSFAN1") (pin "3") (pinfunction "3_3") (pintype "passive+no_connect"))
    )
    (net (code "72") (name "unconnected-(SYSFAN1-Pad4)") (class "Default")
      (node (ref "SYSFAN1") (pin "4") (pinfunction "4_4") (pintype "passive+no_connect"))
    )
    (net (code "73") (name "unconnected-(U1-EP-Pad17)") (class "Default")
      (node (ref "U1") (pin "17") (pinfunction "EP_17") (pintype "passive+no_connect"))
    )
    (net (code "74") (name "unconnected-(U1-NC-Pad1)") (class "Default")
      (node (ref "U1") (pin "1") (pinfunction "NC_1") (pintype "passive+no_connect"))
    )
    (net (code "75") (name "unconnected-(U1-NC-Pad2)") (class "Default")
      (node (ref "U1") (pin "2") (pinfunction "NC_2") (pintype "passive+no_connect"))
    )
    (net (code "76") (name "unconnected-(U1-NC-Pad3)") (class "Default")
      (node (ref "U1") (pin "3") (pinfunction "NC_3") (pintype "passive+no_connect"))
    )
    (net (code "77") (name "unconnected-(U1-NC-Pad4)") (class "Default")
      (node (ref "U1") (pin "4") (pinfunction "NC_4") (pintype "passive+no_connect"))
    )
    (net (code "78") (name "unconnected-(U1-NC-Pad10)") (class "Default")
      (node (ref "U1") (pin "10") (pinfunction "NC_10") (pintype "passive+no_connect"))
    )
    (net (code "79") (name "unconnected-(U1-OUT-Pad15)") (class "Default")
      (node (ref "U1") (pin "15") (pinfunction "OUT_15") (pintype "passive+no_connect"))
    )
    (net (code "80") (name "unconnected-(U1-PUSH-Pad5)") (class "Default")
      (node (ref "U1") (pin "5") (pinfunction "PUSH_5") (pintype "passive+no_connect"))
    )
    (net (code "81") (name "unconnected-(U1-U-Pad11)") (class "Default")
      (node (ref "U1") (pin "11") (pinfunction "U_11") (pintype "passive+no_connect"))
    )
    (net (code "82") (name "unconnected-(U1-V-Pad12)") (class "Default")
      (node (ref "U1") (pin "12") (pinfunction "V_12") (pintype "passive+no_connect"))
    )
    (net (code "83") (name "unconnected-(U1-W-Pad9)") (class "Default")
      (node (ref "U1") (pin "9") (pinfunction "W_9") (pintype "passive+no_connect"))
    )
    (net (code "84") (name "unconnected-(U2-COMPO#-Pad19)") (class "Default")
      (node (ref "U2") (pin "19") (pinfunction "COMPO#_19") (pintype "passive+no_connect"))
    )
    (net (code "85") (name "unconnected-(U2-NC-Pad21)") (class "Default")
      (node (ref "U2") (pin "21") (pinfunction "NC_21") (pintype "passive+no_connect"))
    )
    (net (code "86") (name "unconnected-(U3-ENA-Pad5)") (class "Default")
      (node (ref "U3") (pin "5") (pinfunction "ENA_5") (pintype "passive+no_connect"))
    )
    (net (code "87") (name "unconnected-(U3-NC-Pad2)") (class "Default")
      (node (ref "U3") (pin "2") (pinfunction "NC_2") (pintype "passive+no_connect"))
    )
    (net (code "88") (name "unconnected-(U3-NC-Pad3)") (class "Default")
      (node (ref "U3") (pin "3") (pinfunction "NC_3") (pintype "passive+no_connect"))
    )
    (net (code "89") (name "unconnected-(U4-CFG1-Pad9)") (class "Default")
      (node (ref "U4") (pin "9") (pinfunction "CFG1_9") (pintype "passive+no_connect"))
    )
    (net (code "90") (name "unconnected-(U4-CFG2-Pad2)") (class "Default")
      (node (ref "U4") (pin "2") (pinfunction "CFG2_2") (pintype "passive+no_connect"))
    )
    (net (code "91") (name "unconnected-(U4-CFG3-Pad3)") (class "Default")
      (node (ref "U4") (pin "3") (pinfunction "CFG3_3") (pintype "passive+no_connect"))
    )
    (net (code "92") (name "unconnected-(U4-DM-Pad5)") (class "Default")
      (node (ref "U4") (pin "5") (pinfunction "DM_5") (pintype "passive+no_connect"))
    )
    (net (code "93") (name "unconnected-(U4-DP-Pad4)") (class "Default")
      (node (ref "U4") (pin "4") (pinfunction "DP_4") (pintype "passive+no_connect"))
    )
    (net (code "94") (name "unconnected-(U4-PG-Pad10)") (class "Default")
      (node (ref "U4") (pin "10") (pinfunction "PG_10") (pintype "passive+no_connect"))
    )
    (net (code "95") (name "unconnected-(U5-IO23-Pad37)") (class "Default")
      (node (ref "U5") (pin "37") (pinfunction "IO23_37") (pintype "passive+no_connect"))
    )
    (net (code "96") (name "unconnected-(U5-IO32-Pad8)") (class "Default")
      (node (ref "U5") (pin "8") (pinfunction "IO32_8") (pintype "passive+no_connect"))
    )
    (net (code "97") (name "unconnected-(U5-IO34-Pad6)") (class "Default")
      (node (ref "U5") (pin "6") (pinfunction "IO34_6") (pintype "passive+no_connect"))
    )
    (net (code "98") (name "unconnected-(U5-IO35-Pad7)") (class "Default")
      (node (ref "U5") (pin "7") (pinfunction "IO35_7") (pintype "passive+no_connect"))
    )
    (net (code "99") (name "unconnected-(U5-NC-Pad17)") (class "Default")
      (node (ref "U5") (pin "17") (pinfunction "NC_17") (pintype "passive+no_connect"))
    )
    (net (code "100") (name "unconnected-(U5-NC-Pad18)") (class "Default")
      (node (ref "U5") (pin "18") (pinfunction "NC_18") (pintype "passive+no_connect"))
    )
    (net (code "101") (name "unconnected-(U5-NC-Pad19)") (class "Default")
      (node (ref "U5") (pin "19") (pinfunction "NC_19") (pintype "passive+no_connect"))
    )
    (net (code "102") (name "unconnected-(U5-NC-Pad20)") (class "Default")
      (node (ref "U5") (pin "20") (pinfunction "NC_20") (pintype "passive+no_connect"))
    )
    (net (code "103") (name "unconnected-(U5-NC-Pad21)") (class "Default")
      (node (ref "U5") (pin "21") (pinfunction "NC_21") (pintype "passive+no_connect"))
    )
    (net (code "104") (name "unconnected-(U5-NC-Pad22)") (class "Default")
      (node (ref "U5") (pin "22") (pinfunction "NC_22") (pintype "passive+no_connect"))
    )
    (net (code "105") (name "unconnected-(U5-NC-Pad32)") (class "Default")
      (node (ref "U5") (pin "32") (pinfunction "NC_32") (pintype "passive+no_connect"))
    )
    (net (code "106") (name "unconnected-(U5-SENSOR_VN-Pad5)") (class "Default")
      (node (ref "U5") (pin "5") (pinfunction "SENSOR_VN_5") (pintype "passive+no_connect"))
    )
    (net (code "107") (name "unconnected-(U5-SENSOR_VP-Pad4)") (class "Default")
      (node (ref "U5") (pin "4") (pinfunction "SENSOR_VP_4") (pintype "passive+no_connect"))
    )
    (net (code "108") (name "unconnected-(U6-ENA-Pad5)") (class "Default")
      (node (ref "U6") (pin "5") (pinfunction "ENA_5") (pintype "passive+no_connect"))
    )
    (net (code "109") (name "unconnected-(U6-NC-Pad2)") (class "Default")
      (node (ref "U6") (pin "2") (pinfunction "NC_2") (pintype "passive+no_connect"))
    )
    (net (code "110") (name "unconnected-(U6-NC-Pad3)") (class "Default")
      (node (ref "U6") (pin "3") (pinfunction "NC_3") (pintype "passive+no_connect"))
    )
    (net (code "111") (name "unconnected-(U7-CTS-Pad23)") (class "Default")
      (node (ref "U7") (pin "23") (pinfunction "CTS_23") (pintype "passive+no_connect"))
    )
    (net (code "112") (name "unconnected-(U7-DCD-Pad1)") (class "Default")
      (node (ref "U7") (pin "1") (pinfunction "DCD_1") (pintype "passive+no_connect"))
    )
    (net (code "113") (name "unconnected-(U7-DSR-Pad27)") (class "Default")
      (node (ref "U7") (pin "27") (pinfunction "DSR_27") (pintype "passive+no_connect"))
    )
    (net (code "114") (name "unconnected-(U7-NC-Pad10)") (class "Default")
      (node (ref "U7") (pin "10") (pinfunction "NC_10") (pintype "passive+no_connect"))
    )
    (net (code "115") (name "unconnected-(U7-NC-Pad13)") (class "Default")
      (node (ref "U7") (pin "13") (pinfunction "NC_13") (pintype "passive+no_connect"))
    )
    (net (code "116") (name "unconnected-(U7-NC-Pad14)") (class "Default")
      (node (ref "U7") (pin "14") (pinfunction "NC_14") (pintype "passive+no_connect"))
    )
    (net (code "117") (name "unconnected-(U7-NC-Pad15)") (class "Default")
      (node (ref "U7") (pin "15") (pinfunction "NC_15") (pintype "passive+no_connect"))
    )
    (net (code "118") (name "unconnected-(U7-NC-Pad16)") (class "Default")
      (node (ref "U7") (pin "16") (pinfunction "NC_16") (pintype "passive+no_connect"))
    )
    (net (code "119") (name "unconnected-(U7-NC-Pad17)") (class "Default")
      (node (ref "U7") (pin "17") (pinfunction "NC_17") (pintype "passive+no_connect"))
    )
    (net (code "120") (name "unconnected-(U7-NC-Pad18)") (class "Default")
      (node (ref "U7") (pin "18") (pinfunction "NC_18") (pintype "passive+no_connect"))
    )
    (net (code "121") (name "unconnected-(U7-NC-Pad19)") (class "Default")
      (node (ref "U7") (pin "19") (pinfunction "NC_19") (pintype "passive+no_connect"))
    )
    (net (code "122") (name "unconnected-(U7-NC-Pad20)") (class "Default")
      (node (ref "U7") (pin "20") (pinfunction "NC_20") (pintype "passive+no_connect"))
    )
    (net (code "123") (name "unconnected-(U7-NC-Pad21)") (class "Default")
      (node (ref "U7") (pin "21") (pinfunction "NC_21") (pintype "passive+no_connect"))
    )
    (net (code "124") (name "unconnected-(U7-NC-Pad22)") (class "Default")
      (node (ref "U7") (pin "22") (pinfunction "NC_22") (pintype "passive+no_connect"))
    )
    (net (code "125") (name "unconnected-(U7-RI-Pad2)") (class "Default")
      (node (ref "U7") (pin "2") (pinfunction "RI_2") (pintype "passive+no_connect"))
    )
    (net (code "126") (name "unconnected-(U7-SUSPEND#-Pad11)") (class "Default")
      (node (ref "U7") (pin "11") (pinfunction "SUSPEND#_11") (pintype "passive+no_connect"))
    )
    (net (code "127") (name "unconnected-(U7-SUSPEND-Pad12)") (class "Default")
      (node (ref "U7") (pin "12") (pinfunction "SUSPEND_12") (pintype "passive+no_connect"))
    )
  )
)
